# SFP.net
KiCad netlist of a schematic drawn in Altium Designer
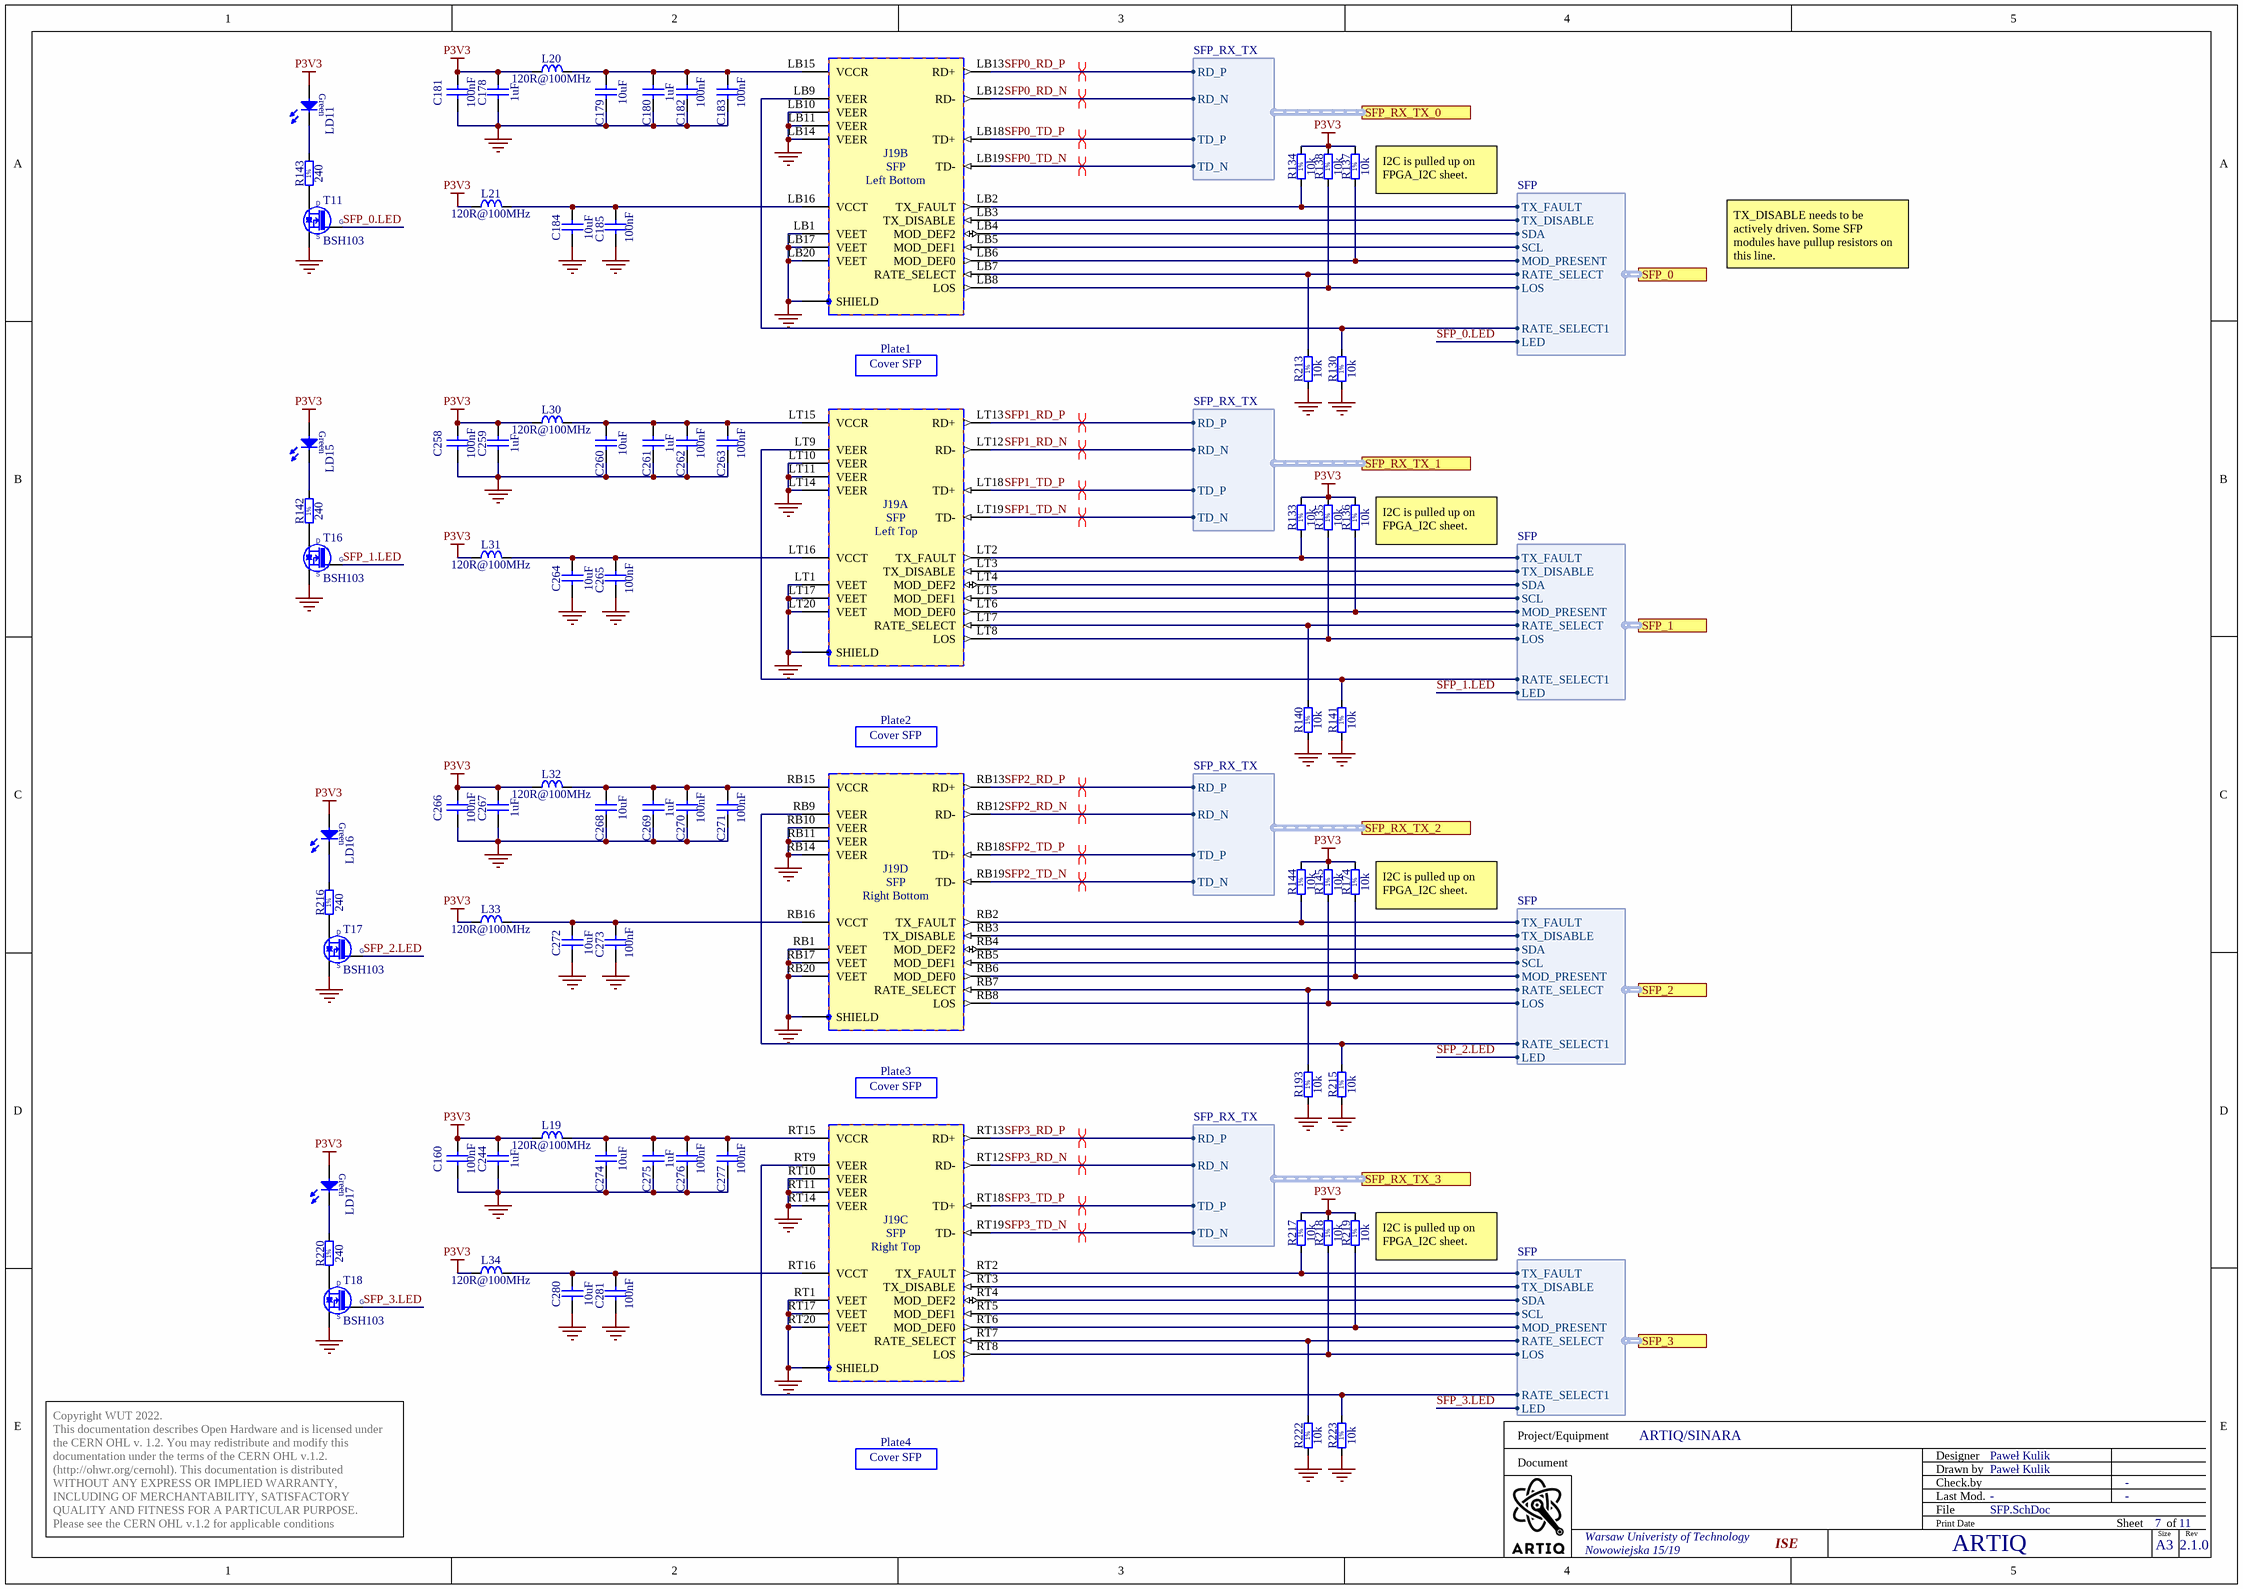
[diagram p0: SFP.SchDoc]

(export (version "E")
  (design (tool "Eeschema 10.0.6"))
  (components
    (comp (ref "C160")
      (value "100nF")
      (footprint "CAPC0603X33N")
      (description "Non-polarised capacitor")
      (fields
        (field (name "PART NUMBER") "CC0201_100NF_6.3V_10%_X5R")
        (field (name "VOLTAGE") "6.3V")
        (field (name "AUTHOR") "CERN DEM JLC")
      )
      (libsource (lib "Capacitors") (part "Capacitor - non polarized"))
    )
    (comp (ref "C178")
      (value "1uF")
      (footprint "CAPC1005X55N")
      (description "Non-polarised capacitor")
      (fields
        (field (name "PART NUMBER") "CC0402_1UF_16V_10%_X5R")
        (field (name "VOLTAGE") "16V")
        (field (name "AUTHOR") "CERN DEM JLC")
      )
      (libsource (lib "Capacitors") (part "Capacitor - non polarized"))
    )
    (comp (ref "C179")
      (value "10uF")
      (footprint "CAPC2012X95N")
      (description "Non-polarised capacitor")
      (fields
        (field (name "PART NUMBER") "CC0805_10UF_25V_10%_X5R")
        (field (name "VOLTAGE") "25V")
        (field (name "AUTHOR") "CERN DEM JLC")
      )
      (libsource (lib "Capacitors") (part "Capacitor - non polarized"))
    )
    (comp (ref "C180")
      (value "1uF")
      (footprint "CAPC1005X55N")
      (description "Non-polarised capacitor")
      (fields
        (field (name "PART NUMBER") "CC0402_1UF_16V_10%_X5R")
        (field (name "VOLTAGE") "16V")
        (field (name "AUTHOR") "CERN DEM JLC")
      )
      (libsource (lib "Capacitors") (part "Capacitor - non polarized"))
    )
    (comp (ref "C181")
      (value "100nF")
      (footprint "CAPC0603X33N")
      (description "Non-polarised capacitor")
      (fields
        (field (name "PART NUMBER") "CC0201_100NF_6.3V_10%_X5R")
        (field (name "VOLTAGE") "6.3V")
        (field (name "AUTHOR") "CERN DEM JLC")
      )
      (libsource (lib "Capacitors") (part "Capacitor - non polarized"))
    )
    (comp (ref "C182")
      (value "100nF")
      (footprint "CAPC0603X33N")
      (description "Non-polarised capacitor")
      (fields
        (field (name "PART NUMBER") "CC0201_100NF_6.3V_10%_X5R")
        (field (name "VOLTAGE") "6.3V")
        (field (name "AUTHOR") "CERN DEM JLC")
      )
      (libsource (lib "Capacitors") (part "Capacitor - non polarized"))
    )
    (comp (ref "C183")
      (value "100nF")
      (footprint "CAPC0603X33N")
      (description "Non-polarised capacitor")
      (fields
        (field (name "PART NUMBER") "CC0201_100NF_6.3V_10%_X5R")
        (field (name "VOLTAGE") "6.3V")
        (field (name "AUTHOR") "CERN DEM JLC")
      )
      (libsource (lib "Capacitors") (part "Capacitor - non polarized"))
    )
    (comp (ref "C184")
      (value "10uF")
      (footprint "CAPC2012X95N")
      (description "Non-polarised capacitor")
      (fields
        (field (name "PART NUMBER") "CC0805_10UF_25V_10%_X5R")
        (field (name "VOLTAGE") "25V")
        (field (name "AUTHOR") "CERN DEM JLC")
      )
      (libsource (lib "Capacitors") (part "Capacitor - non polarized"))
    )
    (comp (ref "C185")
      (value "100nF")
      (footprint "CAPC0603X33N")
      (description "Non-polarised capacitor")
      (fields
        (field (name "PART NUMBER") "CC0201_100NF_6.3V_10%_X5R")
        (field (name "VOLTAGE") "6.3V")
        (field (name "AUTHOR") "CERN DEM JLC")
      )
      (libsource (lib "Capacitors") (part "Capacitor - non polarized"))
    )
    (comp (ref "C244")
      (value "1uF")
      (footprint "CAPC1005X55N")
      (description "Non-polarised capacitor")
      (fields
        (field (name "PART NUMBER") "CC0402_1UF_16V_10%_X5R")
        (field (name "VOLTAGE") "16V")
        (field (name "AUTHOR") "CERN DEM JLC")
      )
      (libsource (lib "Capacitors") (part "Capacitor - non polarized"))
    )
    (comp (ref "C258")
      (value "100nF")
      (footprint "CAPC0603X33N")
      (description "Non-polarised capacitor")
      (fields
        (field (name "PART NUMBER") "CC0201_100NF_6.3V_10%_X5R")
        (field (name "VOLTAGE") "6.3V")
        (field (name "AUTHOR") "CERN DEM JLC")
      )
      (libsource (lib "Capacitors") (part "Capacitor - non polarized"))
    )
    (comp (ref "C259")
      (value "1uF")
      (footprint "CAPC1005X55N")
      (description "Non-polarised capacitor")
      (fields
        (field (name "PART NUMBER") "CC0402_1UF_16V_10%_X5R")
        (field (name "VOLTAGE") "16V")
        (field (name "AUTHOR") "CERN DEM JLC")
      )
      (libsource (lib "Capacitors") (part "Capacitor - non polarized"))
    )
    (comp (ref "C260")
      (value "10uF")
      (footprint "CAPC2012X95N")
      (description "Non-polarised capacitor")
      (fields
        (field (name "PART NUMBER") "CC0805_10UF_25V_10%_X5R")
        (field (name "VOLTAGE") "25V")
        (field (name "AUTHOR") "CERN DEM JLC")
      )
      (libsource (lib "Capacitors") (part "Capacitor - non polarized"))
    )
    (comp (ref "C261")
      (value "1uF")
      (footprint "CAPC1005X55N")
      (description "Non-polarised capacitor")
      (fields
        (field (name "PART NUMBER") "CC0402_1UF_16V_10%_X5R")
        (field (name "VOLTAGE") "16V")
        (field (name "AUTHOR") "CERN DEM JLC")
      )
      (libsource (lib "Capacitors") (part "Capacitor - non polarized"))
    )
    (comp (ref "C262")
      (value "100nF")
      (footprint "CAPC0603X33N")
      (description "Non-polarised capacitor")
      (fields
        (field (name "PART NUMBER") "CC0201_100NF_6.3V_10%_X5R")
        (field (name "VOLTAGE") "6.3V")
        (field (name "AUTHOR") "CERN DEM JLC")
      )
      (libsource (lib "Capacitors") (part "Capacitor - non polarized"))
    )
    (comp (ref "C263")
      (value "100nF")
      (footprint "CAPC0603X33N")
      (description "Non-polarised capacitor")
      (fields
        (field (name "PART NUMBER") "CC0201_100NF_6.3V_10%_X5R")
        (field (name "VOLTAGE") "6.3V")
        (field (name "AUTHOR") "CERN DEM JLC")
      )
      (libsource (lib "Capacitors") (part "Capacitor - non polarized"))
    )
    (comp (ref "C264")
      (value "10uF")
      (footprint "CAPC2012X95N")
      (description "Non-polarised capacitor")
      (fields
        (field (name "PART NUMBER") "CC0805_10UF_25V_10%_X5R")
        (field (name "VOLTAGE") "25V")
        (field (name "AUTHOR") "CERN DEM JLC")
      )
      (libsource (lib "Capacitors") (part "Capacitor - non polarized"))
    )
    (comp (ref "C265")
      (value "100nF")
      (footprint "CAPC0603X33N")
      (description "Non-polarised capacitor")
      (fields
        (field (name "PART NUMBER") "CC0201_100NF_6.3V_10%_X5R")
        (field (name "VOLTAGE") "6.3V")
        (field (name "AUTHOR") "CERN DEM JLC")
      )
      (libsource (lib "Capacitors") (part "Capacitor - non polarized"))
    )
    (comp (ref "C266")
      (value "100nF")
      (footprint "CAPC0603X33N")
      (description "Non-polarised capacitor")
      (fields
        (field (name "PART NUMBER") "CC0201_100NF_6.3V_10%_X5R")
        (field (name "VOLTAGE") "6.3V")
        (field (name "AUTHOR") "CERN DEM JLC")
      )
      (libsource (lib "Capacitors") (part "Capacitor - non polarized"))
    )
    (comp (ref "C267")
      (value "1uF")
      (footprint "CAPC1005X55N")
      (description "Non-polarised capacitor")
      (fields
        (field (name "PART NUMBER") "CC0402_1UF_16V_10%_X5R")
        (field (name "VOLTAGE") "16V")
        (field (name "AUTHOR") "CERN DEM JLC")
      )
      (libsource (lib "Capacitors") (part "Capacitor - non polarized"))
    )
    (comp (ref "C268")
      (value "10uF")
      (footprint "CAPC2012X95N")
      (description "Non-polarised capacitor")
      (fields
        (field (name "PART NUMBER") "CC0805_10UF_25V_10%_X5R")
        (field (name "VOLTAGE") "25V")
        (field (name "AUTHOR") "CERN DEM JLC")
      )
      (libsource (lib "Capacitors") (part "Capacitor - non polarized"))
    )
    (comp (ref "C269")
      (value "1uF")
      (footprint "CAPC1005X55N")
      (description "Non-polarised capacitor")
      (fields
        (field (name "PART NUMBER") "CC0402_1UF_16V_10%_X5R")
        (field (name "VOLTAGE") "16V")
        (field (name "AUTHOR") "CERN DEM JLC")
      )
      (libsource (lib "Capacitors") (part "Capacitor - non polarized"))
    )
    (comp (ref "C270")
      (value "100nF")
      (footprint "CAPC0603X33N")
      (description "Non-polarised capacitor")
      (fields
        (field (name "PART NUMBER") "CC0201_100NF_6.3V_10%_X5R")
        (field (name "VOLTAGE") "6.3V")
        (field (name "AUTHOR") "CERN DEM JLC")
      )
      (libsource (lib "Capacitors") (part "Capacitor - non polarized"))
    )
    (comp (ref "C271")
      (value "100nF")
      (footprint "CAPC0603X33N")
      (description "Non-polarised capacitor")
      (fields
        (field (name "PART NUMBER") "CC0201_100NF_6.3V_10%_X5R")
        (field (name "VOLTAGE") "6.3V")
        (field (name "AUTHOR") "CERN DEM JLC")
      )
      (libsource (lib "Capacitors") (part "Capacitor - non polarized"))
    )
    (comp (ref "C272")
      (value "10uF")
      (footprint "CAPC2012X95N")
      (description "Non-polarised capacitor")
      (fields
        (field (name "PART NUMBER") "CC0805_10UF_25V_10%_X5R")
        (field (name "VOLTAGE") "25V")
        (field (name "AUTHOR") "CERN DEM JLC")
      )
      (libsource (lib "Capacitors") (part "Capacitor - non polarized"))
    )
    (comp (ref "C273")
      (value "100nF")
      (footprint "CAPC0603X33N")
      (description "Non-polarised capacitor")
      (fields
        (field (name "PART NUMBER") "CC0201_100NF_6.3V_10%_X5R")
        (field (name "VOLTAGE") "6.3V")
        (field (name "AUTHOR") "CERN DEM JLC")
      )
      (libsource (lib "Capacitors") (part "Capacitor - non polarized"))
    )
    (comp (ref "C274")
      (value "10uF")
      (footprint "CAPC2012X95N")
      (description "Non-polarised capacitor")
      (fields
        (field (name "PART NUMBER") "CC0805_10UF_25V_10%_X5R")
        (field (name "VOLTAGE") "25V")
        (field (name "AUTHOR") "CERN DEM JLC")
      )
      (libsource (lib "Capacitors") (part "Capacitor - non polarized"))
    )
    (comp (ref "C275")
      (value "1uF")
      (footprint "CAPC1005X55N")
      (description "Non-polarised capacitor")
      (fields
        (field (name "PART NUMBER") "CC0402_1UF_16V_10%_X5R")
        (field (name "VOLTAGE") "16V")
        (field (name "AUTHOR") "CERN DEM JLC")
      )
      (libsource (lib "Capacitors") (part "Capacitor - non polarized"))
    )
    (comp (ref "C276")
      (value "100nF")
      (footprint "CAPC0603X33N")
      (description "Non-polarised capacitor")
      (fields
        (field (name "PART NUMBER") "CC0201_100NF_6.3V_10%_X5R")
        (field (name "VOLTAGE") "6.3V")
        (field (name "AUTHOR") "CERN DEM JLC")
      )
      (libsource (lib "Capacitors") (part "Capacitor - non polarized"))
    )
    (comp (ref "C277")
      (value "100nF")
      (footprint "CAPC0603X33N")
      (description "Non-polarised capacitor")
      (fields
        (field (name "PART NUMBER") "CC0201_100NF_6.3V_10%_X5R")
        (field (name "VOLTAGE") "6.3V")
        (field (name "AUTHOR") "CERN DEM JLC")
      )
      (libsource (lib "Capacitors") (part "Capacitor - non polarized"))
    )
    (comp (ref "C280")
      (value "10uF")
      (footprint "CAPC2012X95N")
      (description "Non-polarised capacitor")
      (fields
        (field (name "PART NUMBER") "CC0805_10UF_25V_10%_X5R")
        (field (name "VOLTAGE") "25V")
        (field (name "AUTHOR") "CERN DEM JLC")
      )
      (libsource (lib "Capacitors") (part "Capacitor - non polarized"))
    )
    (comp (ref "C281")
      (value "100nF")
      (footprint "CAPC0603X33N")
      (description "Non-polarised capacitor")
      (fields
        (field (name "PART NUMBER") "CC0201_100NF_6.3V_10%_X5R")
        (field (name "VOLTAGE") "6.3V")
        (field (name "AUTHOR") "CERN DEM JLC")
      )
      (libsource (lib "Capacitors") (part "Capacitor - non polarized"))
    )
    (comp (ref "J19")
      (value "SFP")
      (footprint "AMPHENOL_UE78B212700321")
      (description "20 Position SFP  Connector (Small Form-factor Pluggable)")
      (fields
        (field (name "PART NUMBER") "AMPHENOL_UE78B212700321")
        (field (name "MANUFACTURER") "AMPHENOL")
        (field (name "AUTHOR") "CERN DEM BC")
      )
      (libsource (lib "Connectors") (part "SFP 2x2 +Cage"))
    )
    (comp (ref "L19")
      (value "120R@100MHz")
      (footprint "INDC1608X65N")
      (description "Inductor")
      (fields
        (field (name "PART NUMBER") "IND0603_MURATA_BLM18SG121TN1D")
        (field (name "POWER") "3A")
        (field (name "AUTHOR") "CERN DEM JLC")
      )
      (libsource (lib "Inductors & Transformers") (part "Inductor"))
    )
    (comp (ref "L20")
      (value "120R@100MHz")
      (footprint "INDC1608X65N")
      (description "Inductor")
      (fields
        (field (name "PART NUMBER") "IND0603_MURATA_BLM18SG121TN1D")
        (field (name "POWER") "3A")
        (field (name "AUTHOR") "CERN DEM JLC")
      )
      (libsource (lib "Inductors & Transformers") (part "Inductor"))
    )
    (comp (ref "L21")
      (value "120R@100MHz")
      (footprint "INDC1608X65N")
      (description "Inductor")
      (fields
        (field (name "PART NUMBER") "IND0603_MURATA_BLM18SG121TN1D")
        (field (name "POWER") "3A")
        (field (name "AUTHOR") "CERN DEM JLC")
      )
      (libsource (lib "Inductors & Transformers") (part "Inductor"))
    )
    (comp (ref "L30")
      (value "120R@100MHz")
      (footprint "INDC1608X65N")
      (description "Inductor")
      (fields
        (field (name "PART NUMBER") "IND0603_MURATA_BLM18SG121TN1D")
        (field (name "POWER") "3A")
        (field (name "AUTHOR") "CERN DEM JLC")
      )
      (libsource (lib "Inductors & Transformers") (part "Inductor"))
    )
    (comp (ref "L31")
      (value "120R@100MHz")
      (footprint "INDC1608X65N")
      (description "Inductor")
      (fields
        (field (name "PART NUMBER") "IND0603_MURATA_BLM18SG121TN1D")
        (field (name "POWER") "3A")
        (field (name "AUTHOR") "CERN DEM JLC")
      )
      (libsource (lib "Inductors & Transformers") (part "Inductor"))
    )
    (comp (ref "L32")
      (value "120R@100MHz")
      (footprint "INDC1608X65N")
      (description "Inductor")
      (fields
        (field (name "PART NUMBER") "IND0603_MURATA_BLM18SG121TN1D")
        (field (name "POWER") "3A")
        (field (name "AUTHOR") "CERN DEM JLC")
      )
      (libsource (lib "Inductors & Transformers") (part "Inductor"))
    )
    (comp (ref "L33")
      (value "120R@100MHz")
      (footprint "INDC1608X65N")
      (description "Inductor")
      (fields
        (field (name "PART NUMBER") "IND0603_MURATA_BLM18SG121TN1D")
        (field (name "POWER") "3A")
        (field (name "AUTHOR") "CERN DEM JLC")
      )
      (libsource (lib "Inductors & Transformers") (part "Inductor"))
    )
    (comp (ref "L34")
      (value "120R@100MHz")
      (footprint "INDC1608X65N")
      (description "Inductor")
      (fields
        (field (name "PART NUMBER") "IND0603_MURATA_BLM18SG121TN1D")
        (field (name "POWER") "3A")
        (field (name "AUTHOR") "CERN DEM JLC")
      )
      (libsource (lib "Inductors & Transformers") (part "Inductor"))
    )
    (comp (ref "LD11")
      (value "Green")
      (footprint "LED_AVAGO_HSME-C120")
      (description "LED Green 1C 2A")
      (fields
        (field (name "PART NUMBER") "LED_AVAGO_HSME-C120")
        (field (name "MANUFACTURER") "AVAGO TECHNOLOGIES")
        (field (name "AUTHOR") "CERN DEM JMW")
      )
      (libsource (lib "ICs And Semiconductors") (part "LED Green 1C 2A"))
    )
    (comp (ref "LD15")
      (value "Green")
      (footprint "LED_AVAGO_HSME-C120")
      (description "LED Green 1C 2A")
      (fields
        (field (name "PART NUMBER") "LED_AVAGO_HSME-C120")
        (field (name "MANUFACTURER") "AVAGO TECHNOLOGIES")
        (field (name "AUTHOR") "CERN DEM JMW")
      )
      (libsource (lib "ICs And Semiconductors") (part "LED Green 1C 2A"))
    )
    (comp (ref "LD16")
      (value "Green")
      (footprint "LED_AVAGO_HSME-C120")
      (description "LED Green 1C 2A")
      (fields
        (field (name "PART NUMBER") "LED_AVAGO_HSME-C120")
        (field (name "MANUFACTURER") "AVAGO TECHNOLOGIES")
        (field (name "AUTHOR") "CERN DEM JMW")
      )
      (libsource (lib "ICs And Semiconductors") (part "LED Green 1C 2A"))
    )
    (comp (ref "LD17")
      (value "Green")
      (footprint "LED_AVAGO_HSME-C120")
      (description "LED Green 1C 2A")
      (fields
        (field (name "PART NUMBER") "LED_AVAGO_HSME-C120")
        (field (name "MANUFACTURER") "AVAGO TECHNOLOGIES")
        (field (name "AUTHOR") "CERN DEM JMW")
      )
      (libsource (lib "ICs And Semiconductors") (part "LED Green 1C 2A"))
    )
    (comp (ref "Plate1")
      (value "Cover SFP")
      (footprint "AMPHENOL_U77A11108000P")
      (description "Plastic Dust Cover SFP Cage")
      (fields
        (field (name "PART NUMBER") "AMPHENOL_U77A11108000P")
        (field (name "MANUFACTURER") "AMPHENOL")
        (field (name "AUTHOR") "CERN DEM BC")
      )
      (libsource (lib "Eletro-mechanical") (part "SFP Cover No Pin"))
    )
    (comp (ref "Plate2")
      (value "Cover SFP")
      (footprint "AMPHENOL_U77A11108000P")
      (description "Plastic Dust Cover SFP Cage")
      (fields
        (field (name "MANUFACTURER") "AMPHENOL")
        (field (name "MANUFACTURER PART NUMBER") "U77A11108000P")
        (field (name "AUTHOR") "CERN DEM BC")
      )
      (libsource (lib "Eletro-mechanical") (part "SFP Cover No Pin"))
    )
    (comp (ref "Plate3")
      (value "Cover SFP")
      (footprint "AMPHENOL_U77A11108000P")
      (description "Plastic Dust Cover SFP Cage")
      (fields
        (field (name "MANUFACTURER") "AMPHENOL")
        (field (name "MANUFACTURER PART NUMBER") "U77A11108000P")
        (field (name "AUTHOR") "CERN DEM BC")
      )
      (libsource (lib "Eletro-mechanical") (part "SFP Cover No Pin"))
    )
    (comp (ref "Plate4")
      (value "Cover SFP")
      (footprint "AMPHENOL_U77A11108000P")
      (description "Plastic Dust Cover SFP Cage")
      (fields
        (field (name "MANUFACTURER") "AMPHENOL")
        (field (name "MANUFACTURER PART NUMBER") "U77A11108000P")
        (field (name "AUTHOR") "CERN DEM BC")
      )
      (libsource (lib "Eletro-mechanical") (part "SFP Cover No Pin"))
    )
    (comp (ref "R130")
      (value "10k")
      (footprint "RESC1005X40N")
      (description "Resistor - 1%")
      (fields
        (field (name "PART NUMBER") "R0402_10K_1%_0.0625W_100PPM")
        (field (name "POWER") "0.0625W")
        (field (name "AUTHOR") "CERN DEM JLC")
      )
      (libsource (lib "Resistors") (part "Resistor - 1%"))
    )
    (comp (ref "R133")
      (value "10k")
      (footprint "RESC1005X40N")
      (description "Resistor - 1%")
      (fields
        (field (name "PART NUMBER") "R0402_10K_1%_0.0625W_100PPM")
        (field (name "POWER") "0.0625W")
        (field (name "AUTHOR") "CERN DEM JLC")
      )
      (libsource (lib "Resistors") (part "Resistor - 1%"))
    )
    (comp (ref "R134")
      (value "10k")
      (footprint "RESC1005X40N")
      (description "Resistor - 1%")
      (fields
        (field (name "PART NUMBER") "R0402_10K_1%_0.0625W_100PPM")
        (field (name "POWER") "0.0625W")
        (field (name "AUTHOR") "CERN DEM JLC")
      )
      (libsource (lib "Resistors") (part "Resistor - 1%"))
    )
    (comp (ref "R135")
      (value "10k")
      (footprint "RESC1005X40N")
      (description "Resistor - 1%")
      (fields
        (field (name "PART NUMBER") "R0402_10K_1%_0.0625W_100PPM")
        (field (name "POWER") "0.0625W")
        (field (name "AUTHOR") "CERN DEM JLC")
      )
      (libsource (lib "Resistors") (part "Resistor - 1%"))
    )
    (comp (ref "R136")
      (value "10k")
      (footprint "RESC1005X40N")
      (description "Resistor - 1%")
      (fields
        (field (name "PART NUMBER") "R0402_10K_1%_0.0625W_100PPM")
        (field (name "POWER") "0.0625W")
        (field (name "AUTHOR") "CERN DEM JLC")
      )
      (libsource (lib "Resistors") (part "Resistor - 1%"))
    )
    (comp (ref "R137")
      (value "10k")
      (footprint "RESC1005X40N")
      (description "Resistor - 1%")
      (fields
        (field (name "PART NUMBER") "R0402_10K_1%_0.0625W_100PPM")
        (field (name "POWER") "0.0625W")
        (field (name "AUTHOR") "CERN DEM JLC")
      )
      (libsource (lib "Resistors") (part "Resistor - 1%"))
    )
    (comp (ref "R138")
      (value "10k")
      (footprint "RESC1005X40N")
      (description "Resistor - 1%")
      (fields
        (field (name "PART NUMBER") "R0402_10K_1%_0.0625W_100PPM")
        (field (name "POWER") "0.0625W")
        (field (name "AUTHOR") "CERN DEM JLC")
      )
      (libsource (lib "Resistors") (part "Resistor - 1%"))
    )
    (comp (ref "R140")
      (value "10k")
      (footprint "RESC1005X40N")
      (description "Resistor - 1%")
      (fields
        (field (name "PART NUMBER") "R0402_10K_1%_0.0625W_100PPM")
        (field (name "POWER") "0.0625W")
        (field (name "AUTHOR") "CERN DEM JLC")
      )
      (libsource (lib "Resistors") (part "Resistor - 1%"))
    )
    (comp (ref "R141")
      (value "10k")
      (footprint "RESC1005X40N")
      (description "Resistor - 1%")
      (fields
        (field (name "PART NUMBER") "R0402_10K_1%_0.0625W_100PPM")
        (field (name "POWER") "0.0625W")
        (field (name "AUTHOR") "CERN DEM JLC")
      )
      (libsource (lib "Resistors") (part "Resistor - 1%"))
    )
    (comp (ref "R142")
      (value "240")
      (footprint "RESC1005X40N")
      (description "Resistor - 1%")
      (fields
        (field (name "PART NUMBER") "R0402_240R_1%_0.0625W_100PPM")
        (field (name "POWER") "0.0625W")
        (field (name "AUTHOR") "CERN DEM JLC")
      )
      (libsource (lib "Resistors") (part "Resistor - 1%"))
    )
    (comp (ref "R143")
      (value "240")
      (footprint "RESC1005X40N")
      (description "Resistor - 1%")
      (fields
        (field (name "PART NUMBER") "R0402_240R_1%_0.0625W_100PPM")
        (field (name "POWER") "0.0625W")
        (field (name "AUTHOR") "CERN DEM JLC")
      )
      (libsource (lib "Resistors") (part "Resistor - 1%"))
    )
    (comp (ref "R144")
      (value "10k")
      (footprint "RESC1005X40N")
      (description "Resistor - 1%")
      (fields
        (field (name "PART NUMBER") "R0402_10K_1%_0.0625W_100PPM")
        (field (name "POWER") "0.0625W")
        (field (name "AUTHOR") "CERN DEM JLC")
      )
      (libsource (lib "Resistors") (part "Resistor - 1%"))
    )
    (comp (ref "R145")
      (value "10k")
      (footprint "RESC1005X40N")
      (description "Resistor - 1%")
      (fields
        (field (name "PART NUMBER") "R0402_10K_1%_0.0625W_100PPM")
        (field (name "POWER") "0.0625W")
        (field (name "AUTHOR") "CERN DEM JLC")
      )
      (libsource (lib "Resistors") (part "Resistor - 1%"))
    )
    (comp (ref "R174")
      (value "10k")
      (footprint "RESC1005X40N")
      (description "Resistor - 1%")
      (fields
        (field (name "PART NUMBER") "R0402_10K_1%_0.0625W_100PPM")
        (field (name "POWER") "0.0625W")
        (field (name "AUTHOR") "CERN DEM JLC")
      )
      (libsource (lib "Resistors") (part "Resistor - 1%"))
    )
    (comp (ref "R193")
      (value "10k")
      (footprint "RESC1005X40N")
      (description "Resistor - 1%")
      (fields
        (field (name "PART NUMBER") "R0402_10K_1%_0.0625W_100PPM")
        (field (name "POWER") "0.0625W")
        (field (name "AUTHOR") "CERN DEM JLC")
      )
      (libsource (lib "Resistors") (part "Resistor - 1%"))
    )
    (comp (ref "R213")
      (value "10k")
      (footprint "RESC1005X40N")
      (description "Resistor - 1%")
      (fields
        (field (name "PART NUMBER") "R0402_10K_1%_0.0625W_100PPM")
        (field (name "POWER") "0.0625W")
        (field (name "AUTHOR") "CERN DEM JLC")
      )
      (libsource (lib "Resistors") (part "Resistor - 1%"))
    )
    (comp (ref "R215")
      (value "10k")
      (footprint "RESC1005X40N")
      (description "Resistor - 1%")
      (fields
        (field (name "PART NUMBER") "R0402_10K_1%_0.0625W_100PPM")
        (field (name "POWER") "0.0625W")
        (field (name "AUTHOR") "CERN DEM JLC")
      )
      (libsource (lib "Resistors") (part "Resistor - 1%"))
    )
    (comp (ref "R216")
      (value "240")
      (footprint "RESC1005X40N")
      (description "Resistor - 1%")
      (fields
        (field (name "PART NUMBER") "R0402_240R_1%_0.0625W_100PPM")
        (field (name "POWER") "0.0625W")
        (field (name "AUTHOR") "CERN DEM JLC")
      )
      (libsource (lib "Resistors") (part "Resistor - 1%"))
    )
    (comp (ref "R217")
      (value "10k")
      (footprint "RESC1005X40N")
      (description "Resistor - 1%")
      (fields
        (field (name "PART NUMBER") "R0402_10K_1%_0.0625W_100PPM")
        (field (name "POWER") "0.0625W")
        (field (name "AUTHOR") "CERN DEM JLC")
      )
      (libsource (lib "Resistors") (part "Resistor - 1%"))
    )
    (comp (ref "R218")
      (value "10k")
      (footprint "RESC1005X40N")
      (description "Resistor - 1%")
      (fields
        (field (name "PART NUMBER") "R0402_10K_1%_0.0625W_100PPM")
        (field (name "POWER") "0.0625W")
        (field (name "AUTHOR") "CERN DEM JLC")
      )
      (libsource (lib "Resistors") (part "Resistor - 1%"))
    )
    (comp (ref "R219")
      (value "10k")
      (footprint "RESC1005X40N")
      (description "Resistor - 1%")
      (fields
        (field (name "PART NUMBER") "R0402_10K_1%_0.0625W_100PPM")
        (field (name "POWER") "0.0625W")
        (field (name "AUTHOR") "CERN DEM JLC")
      )
      (libsource (lib "Resistors") (part "Resistor - 1%"))
    )
    (comp (ref "R220")
      (value "240")
      (footprint "RESC1005X40N")
      (description "Resistor - 1%")
      (fields
        (field (name "PART NUMBER") "R0402_240R_1%_0.0625W_100PPM")
        (field (name "POWER") "0.0625W")
        (field (name "AUTHOR") "CERN DEM JLC")
      )
      (libsource (lib "Resistors") (part "Resistor - 1%"))
    )
    (comp (ref "R222")
      (value "10k")
      (footprint "RESC1005X40N")
      (description "Resistor - 1%")
      (fields
        (field (name "PART NUMBER") "R0402_10K_1%_0.0625W_100PPM")
        (field (name "POWER") "0.0625W")
        (field (name "AUTHOR") "CERN DEM JLC")
      )
      (libsource (lib "Resistors") (part "Resistor - 1%"))
    )
    (comp (ref "R223")
      (value "10k")
      (footprint "RESC1005X40N")
      (description "Resistor - 1%")
      (fields
        (field (name "PART NUMBER") "R0402_10K_1%_0.0625W_100PPM")
        (field (name "POWER") "0.0625W")
        (field (name "AUTHOR") "CERN DEM JLC")
      )
      (libsource (lib "Resistors") (part "Resistor - 1%"))
    )
    (comp (ref "T11")
      (value "BSH103")
      (footprint "SOT95P230X110-3N")
      (description "N-CHANNEL MOSFET WITH DIODE")
      (fields (field (name "MANUFACTURER") "NEXPERIA") (field (name "AUTHOR") "CERN DEM JLC"))
      (libsource (lib "ICs And Semiconductors") (part "N-MOSFET-D 1G 2S 3D"))
    )
    (comp (ref "T16")
      (value "BSH103")
      (footprint "SOT95P230X110-3N")
      (description "N-CHANNEL MOSFET WITH DIODE")
      (fields (field (name "MANUFACTURER") "NEXPERIA") (field (name "AUTHOR") "CERN DEM JLC"))
      (libsource (lib "ICs And Semiconductors") (part "N-MOSFET-D 1G 2S 3D"))
    )
    (comp (ref "T17")
      (value "BSH103")
      (footprint "SOT95P230X110-3N")
      (description "N-CHANNEL MOSFET WITH DIODE")
      (fields (field (name "MANUFACTURER") "NEXPERIA") (field (name "AUTHOR") "CERN DEM JLC"))
      (libsource (lib "ICs And Semiconductors") (part "N-MOSFET-D 1G 2S 3D"))
    )
    (comp (ref "T18")
      (value "BSH103")
      (footprint "SOT95P230X110-3N")
      (description "N-CHANNEL MOSFET WITH DIODE")
      (fields (field (name "MANUFACTURER") "NEXPERIA") (field (name "AUTHOR") "CERN DEM JLC"))
      (libsource (lib "ICs And Semiconductors") (part "N-MOSFET-D 1G 2S 3D"))
    )
  )
  (nets
    (net (code "3") (name "/SFP0_RD_N") (class "Default")
      (node (ref "J19") (pin "LB12") (pinfunction "RD-_LB12") (pintype "output"))
    )
    (net (code "4") (name "/SFP0_RD_P") (class "Default")
      (node (ref "J19") (pin "LB13") (pinfunction "RD+_LB13") (pintype "output"))
    )
    (net (code "5") (name "/SFP0_TD_N") (class "Default")
      (node (ref "J19") (pin "LB19") (pinfunction "TD-_LB19") (pintype "input"))
    )
    (net (code "6") (name "/SFP0_TD_P") (class "Default")
      (node (ref "J19") (pin "LB18") (pinfunction "TD+_LB18") (pintype "input"))
    )
    (net (code "7") (name "/SFP1_RD_N") (class "Default")
      (node (ref "J19") (pin "LT12") (pinfunction "RD-_LT12") (pintype "output"))
    )
    (net (code "8") (name "/SFP1_RD_P") (class "Default")
      (node (ref "J19") (pin "LT13") (pinfunction "RD+_LT13") (pintype "output"))
    )
    (net (code "9") (name "/SFP1_TD_N") (class "Default")
      (node (ref "J19") (pin "LT19") (pinfunction "TD-_LT19") (pintype "input"))
    )
    (net (code "10") (name "/SFP1_TD_P") (class "Default")
      (node (ref "J19") (pin "LT18") (pinfunction "TD+_LT18") (pintype "input"))
    )
    (net (code "11") (name "/SFP2_RD_N") (class "Default")
      (node (ref "J19") (pin "RB12") (pinfunction "RD-_RB12") (pintype "output"))
    )
    (net (code "12") (name "/SFP2_RD_P") (class "Default")
      (node (ref "J19") (pin "RB13") (pinfunction "RD+_RB13") (pintype "output"))
    )
    (net (code "13") (name "/SFP2_TD_N") (class "Default")
      (node (ref "J19") (pin "RB19") (pinfunction "TD-_RB19") (pintype "input"))
    )
    (net (code "14") (name "/SFP2_TD_P") (class "Default")
      (node (ref "J19") (pin "RB18") (pinfunction "TD+_RB18") (pintype "input"))
    )
    (net (code "15") (name "/SFP3_RD_N") (class "Default")
      (node (ref "J19") (pin "RT12") (pinfunction "RD-_RT12") (pintype "output"))
    )
    (net (code "16") (name "/SFP3_RD_P") (class "Default")
      (node (ref "J19") (pin "RT13") (pinfunction "RD+_RT13") (pintype "output"))
    )
    (net (code "17") (name "/SFP3_TD_N") (class "Default")
      (node (ref "J19") (pin "RT19") (pinfunction "TD-_RT19") (pintype "input"))
    )
    (net (code "18") (name "/SFP3_TD_P") (class "Default")
      (node (ref "J19") (pin "RT18") (pinfunction "TD+_RT18") (pintype "input"))
    )
    (net (code "19") (name "/SFP_0.LED") (class "Default")
      (node (ref "T11") (pin "1") (pinfunction "G_1") (pintype "passive"))
    )
    (net (code "20") (name "/SFP_1.LED") (class "Default")
      (node (ref "T16") (pin "1") (pinfunction "G_1") (pintype "passive"))
    )
    (net (code "21") (name "/SFP_2.LED") (class "Default")
      (node (ref "T17") (pin "1") (pinfunction "G_1") (pintype "passive"))
    )
    (net (code "22") (name "/SFP_3.LED") (class "Default")
      (node (ref "T18") (pin "1") (pinfunction "G_1") (pintype "passive"))
    )
    (net (code "25") (name "GND") (class "Default")
      (node (ref "C160") (pin "1") (pinfunction "1_1") (pintype "passive"))
      (node (ref "C178") (pin "1") (pinfunction "1_1") (pintype "passive"))
      (node (ref "C179") (pin "1") (pinfunction "1_1") (pintype "passive"))
      (node (ref "C180") (pin "1") (pinfunction "1_1") (pintype "passive"))
      (node (ref "C181") (pin "1") (pinfunction "1_1") (pintype "passive"))
      (node (ref "C182") (pin "1") (pinfunction "1_1") (pintype "passive"))
      (node (ref "C183") (pin "1") (pinfunction "1_1") (pintype "passive"))
      (node (ref "C184") (pin "1") (pinfunction "1_1") (pintype "passive"))
      (node (ref "C185") (pin "1") (pinfunction "1_1") (pintype "passive"))
      (node (ref "C244") (pin "1") (pinfunction "1_1") (pintype "passive"))
      (node (ref "C258") (pin "1") (pinfunction "1_1") (pintype "passive"))
      (node (ref "C259") (pin "1") (pinfunction "1_1") (pintype "passive"))
      (node (ref "C260") (pin "1") (pinfunction "1_1") (pintype "passive"))
      (node (ref "C261") (pin "1") (pinfunction "1_1") (pintype "passive"))
      (node (ref "C262") (pin "1") (pinfunction "1_1") (pintype "passive"))
      (node (ref "C263") (pin "1") (pinfunction "1_1") (pintype "passive"))
      (node (ref "C264") (pin "1") (pinfunction "1_1") (pintype "passive"))
      (node (ref "C265") (pin "1") (pinfunction "1_1") (pintype "passive"))
      (node (ref "C266") (pin "1") (pinfunction "1_1") (pintype "passive"))
      (node (ref "C267") (pin "1") (pinfunction "1_1") (pintype "passive"))
      (node (ref "C268") (pin "1") (pinfunction "1_1") (pintype "passive"))
      (node (ref "C269") (pin "1") (pinfunction "1_1") (pintype "passive"))
      (node (ref "C270") (pin "1") (pinfunction "1_1") (pintype "passive"))
      (node (ref "C271") (pin "1") (pinfunction "1_1") (pintype "passive"))
      (node (ref "C272") (pin "1") (pinfunction "1_1") (pintype "passive"))
      (node (ref "C273") (pin "1") (pinfunction "1_1") (pintype "passive"))
      (node (ref "C274") (pin "1") (pinfunction "1_1") (pintype "passive"))
      (node (ref "C275") (pin "1") (pinfunction "1_1") (pintype "passive"))
      (node (ref "C276") (pin "1") (pinfunction "1_1") (pintype "passive"))
      (node (ref "C277") (pin "1") (pinfunction "1_1") (pintype "passive"))
      (node (ref "C280") (pin "1") (pinfunction "1_1") (pintype "passive"))
      (node (ref "C281") (pin "1") (pinfunction "1_1") (pintype "passive"))
      (node (ref "J19") (pin "LB1") (pinfunction "VEET_LB1") (pintype "power_in"))
      (node (ref "J19") (pin "LB10") (pinfunction "VEER_LB10") (pintype "power_in"))
      (node (ref "J19") (pin "LB11") (pinfunction "VEER_LB11") (pintype "power_in"))
      (node (ref "J19") (pin "LB14") (pinfunction "VEER_LB14") (pintype "power_in"))
      (node (ref "J19") (pin "LB17") (pinfunction "VEET_LB17") (pintype "power_in"))
      (node (ref "J19") (pin "LB20") (pinfunction "VEET_LB20") (pintype "power_in"))
      (node (ref "J19") (pin "LT1") (pinfunction "VEET_LT1") (pintype "power_in"))
      (node (ref "J19") (pin "LT10") (pinfunction "VEER_LT10") (pintype "power_in"))
      (node (ref "J19") (pin "LT11") (pinfunction "VEER_LT11") (pintype "power_in"))
      (node (ref "J19") (pin "LT14") (pinfunction "VEER_LT14") (pintype "power_in"))
      (node (ref "J19") (pin "LT17") (pinfunction "VEET_LT17") (pintype "power_in"))
      (node (ref "J19") (pin "LT20") (pinfunction "VEET_LT20") (pintype "power_in"))
      (node (ref "J19") (pin "RB1") (pinfunction "VEET_RB1") (pintype "power_in"))
      (node (ref "J19") (pin "RB10") (pinfunction "VEER_RB10") (pintype "power_in"))
      (node (ref "J19") (pin "RB11") (pinfunction "VEER_RB11") (pintype "power_in"))
      (node (ref "J19") (pin "RB14") (pinfunction "VEER_RB14") (pintype "power_in"))
      (node (ref "J19") (pin "RB17") (pinfunction "VEET_RB17") (pintype "power_in"))
      (node (ref "J19") (pin "RB20") (pinfunction "VEET_RB20") (pintype "power_in"))
      (node (ref "J19") (pin "RT1") (pinfunction "VEET_RT1") (pintype "power_in"))
      (node (ref "J19") (pin "RT10") (pinfunction "VEER_RT10") (pintype "power_in"))
      (node (ref "J19") (pin "RT11") (pinfunction "VEER_RT11") (pintype "power_in"))
      (node (ref "J19") (pin "RT14") (pinfunction "VEER_RT14") (pintype "power_in"))
      (node (ref "J19") (pin "RT17") (pinfunction "VEET_RT17") (pintype "power_in"))
      (node (ref "J19") (pin "RT20") (pinfunction "VEET_RT20") (pintype "power_in"))
      (node (ref "J19") (pin "SHIELD") (pinfunction "SHIELD_SHIELD") (pintype "power_in"))
      (node (ref "R130") (pin "1") (pinfunction "1_1") (pintype "passive"))
      (node (ref "R140") (pin "1") (pinfunction "1_1") (pintype "passive"))
      (node (ref "R141") (pin "1") (pinfunction "1_1") (pintype "passive"))
      (node (ref "R193") (pin "1") (pinfunction "1_1") (pintype "passive"))
      (node (ref "R213") (pin "1") (pinfunction "1_1") (pintype "passive"))
      (node (ref "R215") (pin "1") (pinfunction "1_1") (pintype "passive"))
      (node (ref "R222") (pin "1") (pinfunction "1_1") (pintype "passive"))
      (node (ref "R223") (pin "1") (pinfunction "1_1") (pintype "passive"))
      (node (ref "T11") (pin "2") (pinfunction "S_2") (pintype "passive"))
      (node (ref "T16") (pin "2") (pinfunction "S_2") (pintype "passive"))
      (node (ref "T17") (pin "2") (pinfunction "S_2") (pintype "passive"))
      (node (ref "T18") (pin "2") (pinfunction "S_2") (pintype "passive"))
    )
    (net (code "26") (name "Net-(J19A-LOS)") (class "Default")
      (node (ref "J19") (pin "LT8") (pinfunction "LOS_LT8") (pintype "output"))
      (node (ref "R135") (pin "1") (pinfunction "1_1") (pintype "passive"))
    )
    (net (code "27") (name "Net-(J19A-MOD_DEF0)") (class "Default")
      (node (ref "J19") (pin "LT6") (pinfunction "MOD_DEF0_LT6") (pintype "output"))
      (node (ref "R136") (pin "1") (pinfunction "1_1") (pintype "passive"))
    )
    (net (code "28") (name "Net-(J19A-RATE_SELECT)") (class "Default")
      (node (ref "J19") (pin "LT7") (pinfunction "RATE_SELECT_LT7") (pintype "input"))
      (node (ref "R140") (pin "2") (pinfunction "2_2") (pintype "passive"))
    )
    (net (code "29") (name "Net-(J19A-TX_FAULT)") (class "Default")
      (node (ref "J19") (pin "LT2") (pinfunction "TX_FAULT_LT2") (pintype "output"))
      (node (ref "R133") (pin "1") (pinfunction "1_1") (pintype "passive"))
    )
    (net (code "30") (name "Net-(J19A-VCCR)") (class "Default")
      (node (ref "C260") (pin "2") (pinfunction "2_2") (pintype "passive"))
      (node (ref "C261") (pin "2") (pinfunction "2_2") (pintype "passive"))
      (node (ref "C262") (pin "2") (pinfunction "2_2") (pintype "passive"))
      (node (ref "C263") (pin "2") (pinfunction "2_2") (pintype "passive"))
      (node (ref "J19") (pin "LT15") (pinfunction "VCCR_LT15") (pintype "power_in"))
      (node (ref "L30") (pin "2") (pinfunction "2_2") (pintype "passive"))
    )
    (net (code "31") (name "Net-(J19A-VCCT)") (class "Default")
      (node (ref "C264") (pin "2") (pinfunction "2_2") (pintype "passive"))
      (node (ref "C265") (pin "2") (pinfunction "2_2") (pintype "passive"))
      (node (ref "J19") (pin "LT16") (pinfunction "VCCT_LT16") (pintype "power_in"))
      (node (ref "L31") (pin "2") (pinfunction "2_2") (pintype "passive"))
    )
    (net (code "32") (name "Net-(J19A-VEER-PadLT9)") (class "Default")
      (node (ref "J19") (pin "LT9") (pinfunction "VEER_LT9") (pintype "power_in"))
      (node (ref "R141") (pin "2") (pinfunction "2_2") (pintype "passive"))
    )
    (net (code "33") (name "Net-(J19B-LOS)") (class "Default")
      (node (ref "J19") (pin "LB8") (pinfunction "LOS_LB8") (pintype "output"))
      (node (ref "R138") (pin "1") (pinfunction "1_1") (pintype "passive"))
    )
    (net (code "34") (name "Net-(J19B-MOD_DEF0)") (class "Default")
      (node (ref "J19") (pin "LB6") (pinfunction "MOD_DEF0_LB6") (pintype "output"))
      (node (ref "R137") (pin "1") (pinfunction "1_1") (pintype "passive"))
    )
    (net (code "35") (name "Net-(J19B-RATE_SELECT)") (class "Default")
      (node (ref "J19") (pin "LB7") (pinfunction "RATE_SELECT_LB7") (pintype "input"))
      (node (ref "R213") (pin "2") (pinfunction "2_2") (pintype "passive"))
    )
    (net (code "36") (name "Net-(J19B-TX_FAULT)") (class "Default")
      (node (ref "J19") (pin "LB2") (pinfunction "TX_FAULT_LB2") (pintype "output"))
      (node (ref "R134") (pin "1") (pinfunction "1_1") (pintype "passive"))
    )
    (net (code "37") (name "Net-(J19B-VCCR)") (class "Default")
      (node (ref "C179") (pin "2") (pinfunction "2_2") (pintype "passive"))
      (node (ref "C180") (pin "2") (pinfunction "2_2") (pintype "passive"))
      (node (ref "C182") (pin "2") (pinfunction "2_2") (pintype "passive"))
      (node (ref "C183") (pin "2") (pinfunction "2_2") (pintype "passive"))
      (node (ref "J19") (pin "LB15") (pinfunction "VCCR_LB15") (pintype "power_in"))
      (node (ref "L20") (pin "2") (pinfunction "2_2") (pintype "passive"))
    )
    (net (code "38") (name "Net-(J19B-VCCT)") (class "Default")
      (node (ref "C184") (pin "2") (pinfunction "2_2") (pintype "passive"))
      (node (ref "C185") (pin "2") (pinfunction "2_2") (pintype "passive"))
      (node (ref "J19") (pin "LB16") (pinfunction "VCCT_LB16") (pintype "power_in"))
      (node (ref "L21") (pin "2") (pinfunction "2_2") (pintype "passive"))
    )
    (net (code "39") (name "Net-(J19B-VEER-PadLB9)") (class "Default")
      (node (ref "J19") (pin "LB9") (pinfunction "VEER_LB9") (pintype "power_in"))
      (node (ref "R130") (pin "2") (pinfunction "2_2") (pintype "passive"))
    )
    (net (code "40") (name "Net-(J19C-LOS)") (class "Default")
      (node (ref "J19") (pin "RT8") (pinfunction "LOS_RT8") (pintype "output"))
      (node (ref "R218") (pin "1") (pinfunction "1_1") (pintype "passive"))
    )
    (net (code "41") (name "Net-(J19C-MOD_DEF0)") (class "Default")
      (node (ref "J19") (pin "RT6") (pinfunction "MOD_DEF0_RT6") (pintype "output"))
      (node (ref "R219") (pin "1") (pinfunction "1_1") (pintype "passive"))
    )
    (net (code "42") (name "Net-(J19C-RATE_SELECT)") (class "Default")
      (node (ref "J19") (pin "RT7") (pinfunction "RATE_SELECT_RT7") (pintype "input"))
      (node (ref "R222") (pin "2") (pinfunction "2_2") (pintype "passive"))
    )
    (net (code "43") (name "Net-(J19C-TX_FAULT)") (class "Default")
      (node (ref "J19") (pin "RT2") (pinfunction "TX_FAULT_RT2") (pintype "output"))
      (node (ref "R217") (pin "1") (pinfunction "1_1") (pintype "passive"))
    )
    (net (code "44") (name "Net-(J19C-VCCR)") (class "Default")
      (node (ref "C274") (pin "2") (pinfunction "2_2") (pintype "passive"))
      (node (ref "C275") (pin "2") (pinfunction "2_2") (pintype "passive"))
      (node (ref "C276") (pin "2") (pinfunction "2_2") (pintype "passive"))
      (node (ref "C277") (pin "2") (pinfunction "2_2") (pintype "passive"))
      (node (ref "J19") (pin "RT15") (pinfunction "VCCR_RT15") (pintype "power_in"))
      (node (ref "L19") (pin "2") (pinfunction "2_2") (pintype "passive"))
    )
    (net (code "45") (name "Net-(J19C-VCCT)") (class "Default")
      (node (ref "C280") (pin "2") (pinfunction "2_2") (pintype "passive"))
      (node (ref "C281") (pin "2") (pinfunction "2_2") (pintype "passive"))
      (node (ref "J19") (pin "RT16") (pinfunction "VCCT_RT16") (pintype "power_in"))
      (node (ref "L34") (pin "2") (pinfunction "2_2") (pintype "passive"))
    )
    (net (code "46") (name "Net-(J19C-VEER-PadRT9)") (class "Default")
      (node (ref "J19") (pin "RT9") (pinfunction "VEER_RT9") (pintype "power_in"))
      (node (ref "R223") (pin "2") (pinfunction "2_2") (pintype "passive"))
    )
    (net (code "47") (name "Net-(J19D-LOS)") (class "Default")
      (node (ref "J19") (pin "RB8") (pinfunction "LOS_RB8") (pintype "output"))
      (node (ref "R145") (pin "1") (pinfunction "1_1") (pintype "passive"))
    )
    (net (code "48") (name "Net-(J19D-MOD_DEF0)") (class "Default")
      (node (ref "J19") (pin "RB6") (pinfunction "MOD_DEF0_RB6") (pintype "output"))
      (node (ref "R174") (pin "1") (pinfunction "1_1") (pintype "passive"))
    )
    (net (code "49") (name "Net-(J19D-RATE_SELECT)") (class "Default")
      (node (ref "J19") (pin "RB7") (pinfunction "RATE_SELECT_RB7") (pintype "input"))
      (node (ref "R193") (pin "2") (pinfunction "2_2") (pintype "passive"))
    )
    (net (code "50") (name "Net-(J19D-TX_FAULT)") (class "Default")
      (node (ref "J19") (pin "RB2") (pinfunction "TX_FAULT_RB2") (pintype "output"))
      (node (ref "R144") (pin "1") (pinfunction "1_1") (pintype "passive"))
    )
    (net (code "51") (name "Net-(J19D-VCCR)") (class "Default")
      (node (ref "C268") (pin "2") (pinfunction "2_2") (pintype "passive"))
      (node (ref "C269") (pin "2") (pinfunction "2_2") (pintype "passive"))
      (node (ref "C270") (pin "2") (pinfunction "2_2") (pintype "passive"))
      (node (ref "C271") (pin "2") (pinfunction "2_2") (pintype "passive"))
      (node (ref "J19") (pin "RB15") (pinfunction "VCCR_RB15") (pintype "power_in"))
      (node (ref "L32") (pin "2") (pinfunction "2_2") (pintype "passive"))
    )
    (net (code "52") (name "Net-(J19D-VCCT)") (class "Default")
      (node (ref "C272") (pin "2") (pinfunction "2_2") (pintype "passive"))
      (node (ref "C273") (pin "2") (pinfunction "2_2") (pintype "passive"))
      (node (ref "J19") (pin "RB16") (pinfunction "VCCT_RB16") (pintype "power_in"))
      (node (ref "L33") (pin "2") (pinfunction "2_2") (pintype "passive"))
    )
    (net (code "53") (name "Net-(J19D-VEER-PadRB9)") (class "Default")
      (node (ref "J19") (pin "RB9") (pinfunction "VEER_RB9") (pintype "power_in"))
      (node (ref "R215") (pin "2") (pinfunction "2_2") (pintype "passive"))
    )
    (net (code "54") (name "Net-(LD11-C)") (class "Default")
      (node (ref "LD11") (pin "1") (pinfunction "C_1") (pintype "passive"))
      (node (ref "R143") (pin "2") (pinfunction "2_2") (pintype "passive"))
    )
    (net (code "55") (name "Net-(LD15-C)") (class "Default")
      (node (ref "LD15") (pin "1") (pinfunction "C_1") (pintype "passive"))
      (node (ref "R142") (pin "2") (pinfunction "2_2") (pintype "passive"))
    )
    (net (code "56") (name "Net-(LD16-C)") (class "Default")
      (node (ref "LD16") (pin "1") (pinfunction "C_1") (pintype "passive"))
      (node (ref "R216") (pin "2") (pinfunction "2_2") (pintype "passive"))
    )
    (net (code "57") (name "Net-(LD17-C)") (class "Default")
      (node (ref "LD17") (pin "1") (pinfunction "C_1") (pintype "passive"))
      (node (ref "R220") (pin "2") (pinfunction "2_2") (pintype "passive"))
    )
    (net (code "58") (name "Net-(T11-D)") (class "Default")
      (node (ref "R143") (pin "1") (pinfunction "1_1") (pintype "passive"))
      (node (ref "T11") (pin "3") (pinfunction "D_3") (pintype "passive"))
    )
    (net (code "59") (name "Net-(T16-D)") (class "Default")
      (node (ref "R142") (pin "1") (pinfunction "1_1") (pintype "passive"))
      (node (ref "T16") (pin "3") (pinfunction "D_3") (pintype "passive"))
    )
    (net (code "60") (name "Net-(T17-D)") (class "Default")
      (node (ref "R216") (pin "1") (pinfunction "1_1") (pintype "passive"))
      (node (ref "T17") (pin "3") (pinfunction "D_3") (pintype "passive"))
    )
    (net (code "61") (name "Net-(T18-D)") (class "Default")
      (node (ref "R220") (pin "1") (pinfunction "1_1") (pintype "passive"))
      (node (ref "T18") (pin "3") (pinfunction "D_3") (pintype "passive"))
    )
    (net (code "62") (name "P3V3") (class "Default")
      (node (ref "C160") (pin "2") (pinfunction "2_2") (pintype "passive"))
      (node (ref "C178") (pin "2") (pinfunction "2_2") (pintype "passive"))
      (node (ref "C181") (pin "2") (pinfunction "2_2") (pintype "passive"))
      (node (ref "C244") (pin "2") (pinfunction "2_2") (pintype "passive"))
      (node (ref "C258") (pin "2") (pinfunction "2_2") (pintype "passive"))
      (node (ref "C259") (pin "2") (pinfunction "2_2") (pintype "passive"))
      (node (ref "C266") (pin "2") (pinfunction "2_2") (pintype "passive"))
      (node (ref "C267") (pin "2") (pinfunction "2_2") (pintype "passive"))
      (node (ref "L19") (pin "1") (pinfunction "1_1") (pintype "passive"))
      (node (ref "L20") (pin "1") (pinfunction "1_1") (pintype "passive"))
      (node (ref "L21") (pin "1") (pinfunction "1_1") (pintype "passive"))
      (node (ref "L30") (pin "1") (pinfunction "1_1") (pintype "passive"))
      (node (ref "L31") (pin "1") (pinfunction "1_1") (pintype "passive"))
      (node (ref "L32") (pin "1") (pinfunction "1_1") (pintype "passive"))
      (node (ref "L33") (pin "1") (pinfunction "1_1") (pintype "passive"))
      (node (ref "L34") (pin "1") (pinfunction "1_1") (pintype "passive"))
      (node (ref "LD11") (pin "2") (pinfunction "A_2") (pintype "passive"))
      (node (ref "LD15") (pin "2") (pinfunction "A_2") (pintype "passive"))
      (node (ref "LD16") (pin "2") (pinfunction "A_2") (pintype "passive"))
      (node (ref "LD17") (pin "2") (pinfunction "A_2") (pintype "passive"))
      (node (ref "R133") (pin "2") (pinfunction "2_2") (pintype "passive"))
      (node (ref "R134") (pin "2") (pinfunction "2_2") (pintype "passive"))
      (node (ref "R135") (pin "2") (pinfunction "2_2") (pintype "passive"))
      (node (ref "R136") (pin "2") (pinfunction "2_2") (pintype "passive"))
      (node (ref "R137") (pin "2") (pinfunction "2_2") (pintype "passive"))
      (node (ref "R138") (pin "2") (pinfunction "2_2") (pintype "passive"))
      (node (ref "R144") (pin "2") (pinfunction "2_2") (pintype "passive"))
      (node (ref "R145") (pin "2") (pinfunction "2_2") (pintype "passive"))
      (node (ref "R174") (pin "2") (pinfunction "2_2") (pintype "passive"))
      (node (ref "R217") (pin "2") (pinfunction "2_2") (pintype "passive"))
      (node (ref "R218") (pin "2") (pinfunction "2_2") (pintype "passive"))
      (node (ref "R219") (pin "2") (pinfunction "2_2") (pintype "passive"))
    )
    (net (code "63") (name "unconnected-(J19A-MOD_DEF1-PadLT5)") (class "Default")
      (node (ref "J19") (pin "LT5") (pinfunction "MOD_DEF1_LT5") (pintype "input"))
    )
    (net (code "64") (name "unconnected-(J19A-MOD_DEF2-PadLT4)") (class "Default")
      (node (ref "J19") (pin "LT4") (pinfunction "MOD_DEF2_LT4") (pintype "bidirectional"))
    )
    (net (code "65") (name "unconnected-(J19A-TX_DISABLE-PadLT3)") (class "Default")
      (node (ref "J19") (pin "LT3") (pinfunction "TX_DISABLE_LT3") (pintype "input"))
    )
    (net (code "66") (name "unconnected-(J19B-MOD_DEF1-PadLB5)") (class "Default")
      (node (ref "J19") (pin "LB5") (pinfunction "MOD_DEF1_LB5") (pintype "input"))
    )
    (net (code "67") (name "unconnected-(J19B-MOD_DEF2-PadLB4)") (class "Default")
      (node (ref "J19") (pin "LB4") (pinfunction "MOD_DEF2_LB4") (pintype "bidirectional"))
    )
    (net (code "68") (name "unconnected-(J19B-TX_DISABLE-PadLB3)") (class "Default")
      (node (ref "J19") (pin "LB3") (pinfunction "TX_DISABLE_LB3") (pintype "input"))
    )
    (net (code "69") (name "unconnected-(J19C-MOD_DEF1-PadRT5)") (class "Default")
      (node (ref "J19") (pin "RT5") (pinfunction "MOD_DEF1_RT5") (pintype "input"))
    )
    (net (code "70") (name "unconnected-(J19C-MOD_DEF2-PadRT4)") (class "Default")
      (node (ref "J19") (pin "RT4") (pinfunction "MOD_DEF2_RT4") (pintype "bidirectional"))
    )
    (net (code "71") (name "unconnected-(J19C-TX_DISABLE-PadRT3)") (class "Default")
      (node (ref "J19") (pin "RT3") (pinfunction "TX_DISABLE_RT3") (pintype "input"))
    )
    (net (code "72") (name "unconnected-(J19D-MOD_DEF1-PadRB5)") (class "Default")
      (node (ref "J19") (pin "RB5") (pinfunction "MOD_DEF1_RB5") (pintype "input"))
    )
    (net (code "73") (name "unconnected-(J19D-MOD_DEF2-PadRB4)") (class "Default")
      (node (ref "J19") (pin "RB4") (pinfunction "MOD_DEF2_RB4") (pintype "bidirectional"))
    )
    (net (code "74") (name "unconnected-(J19D-TX_DISABLE-PadRB3)") (class "Default")
      (node (ref "J19") (pin "RB3") (pinfunction "TX_DISABLE_RB3") (pintype "input"))
    )
  )
)
